# circuit.net
KiCad netlist of a schematic drawn in EasyEDA
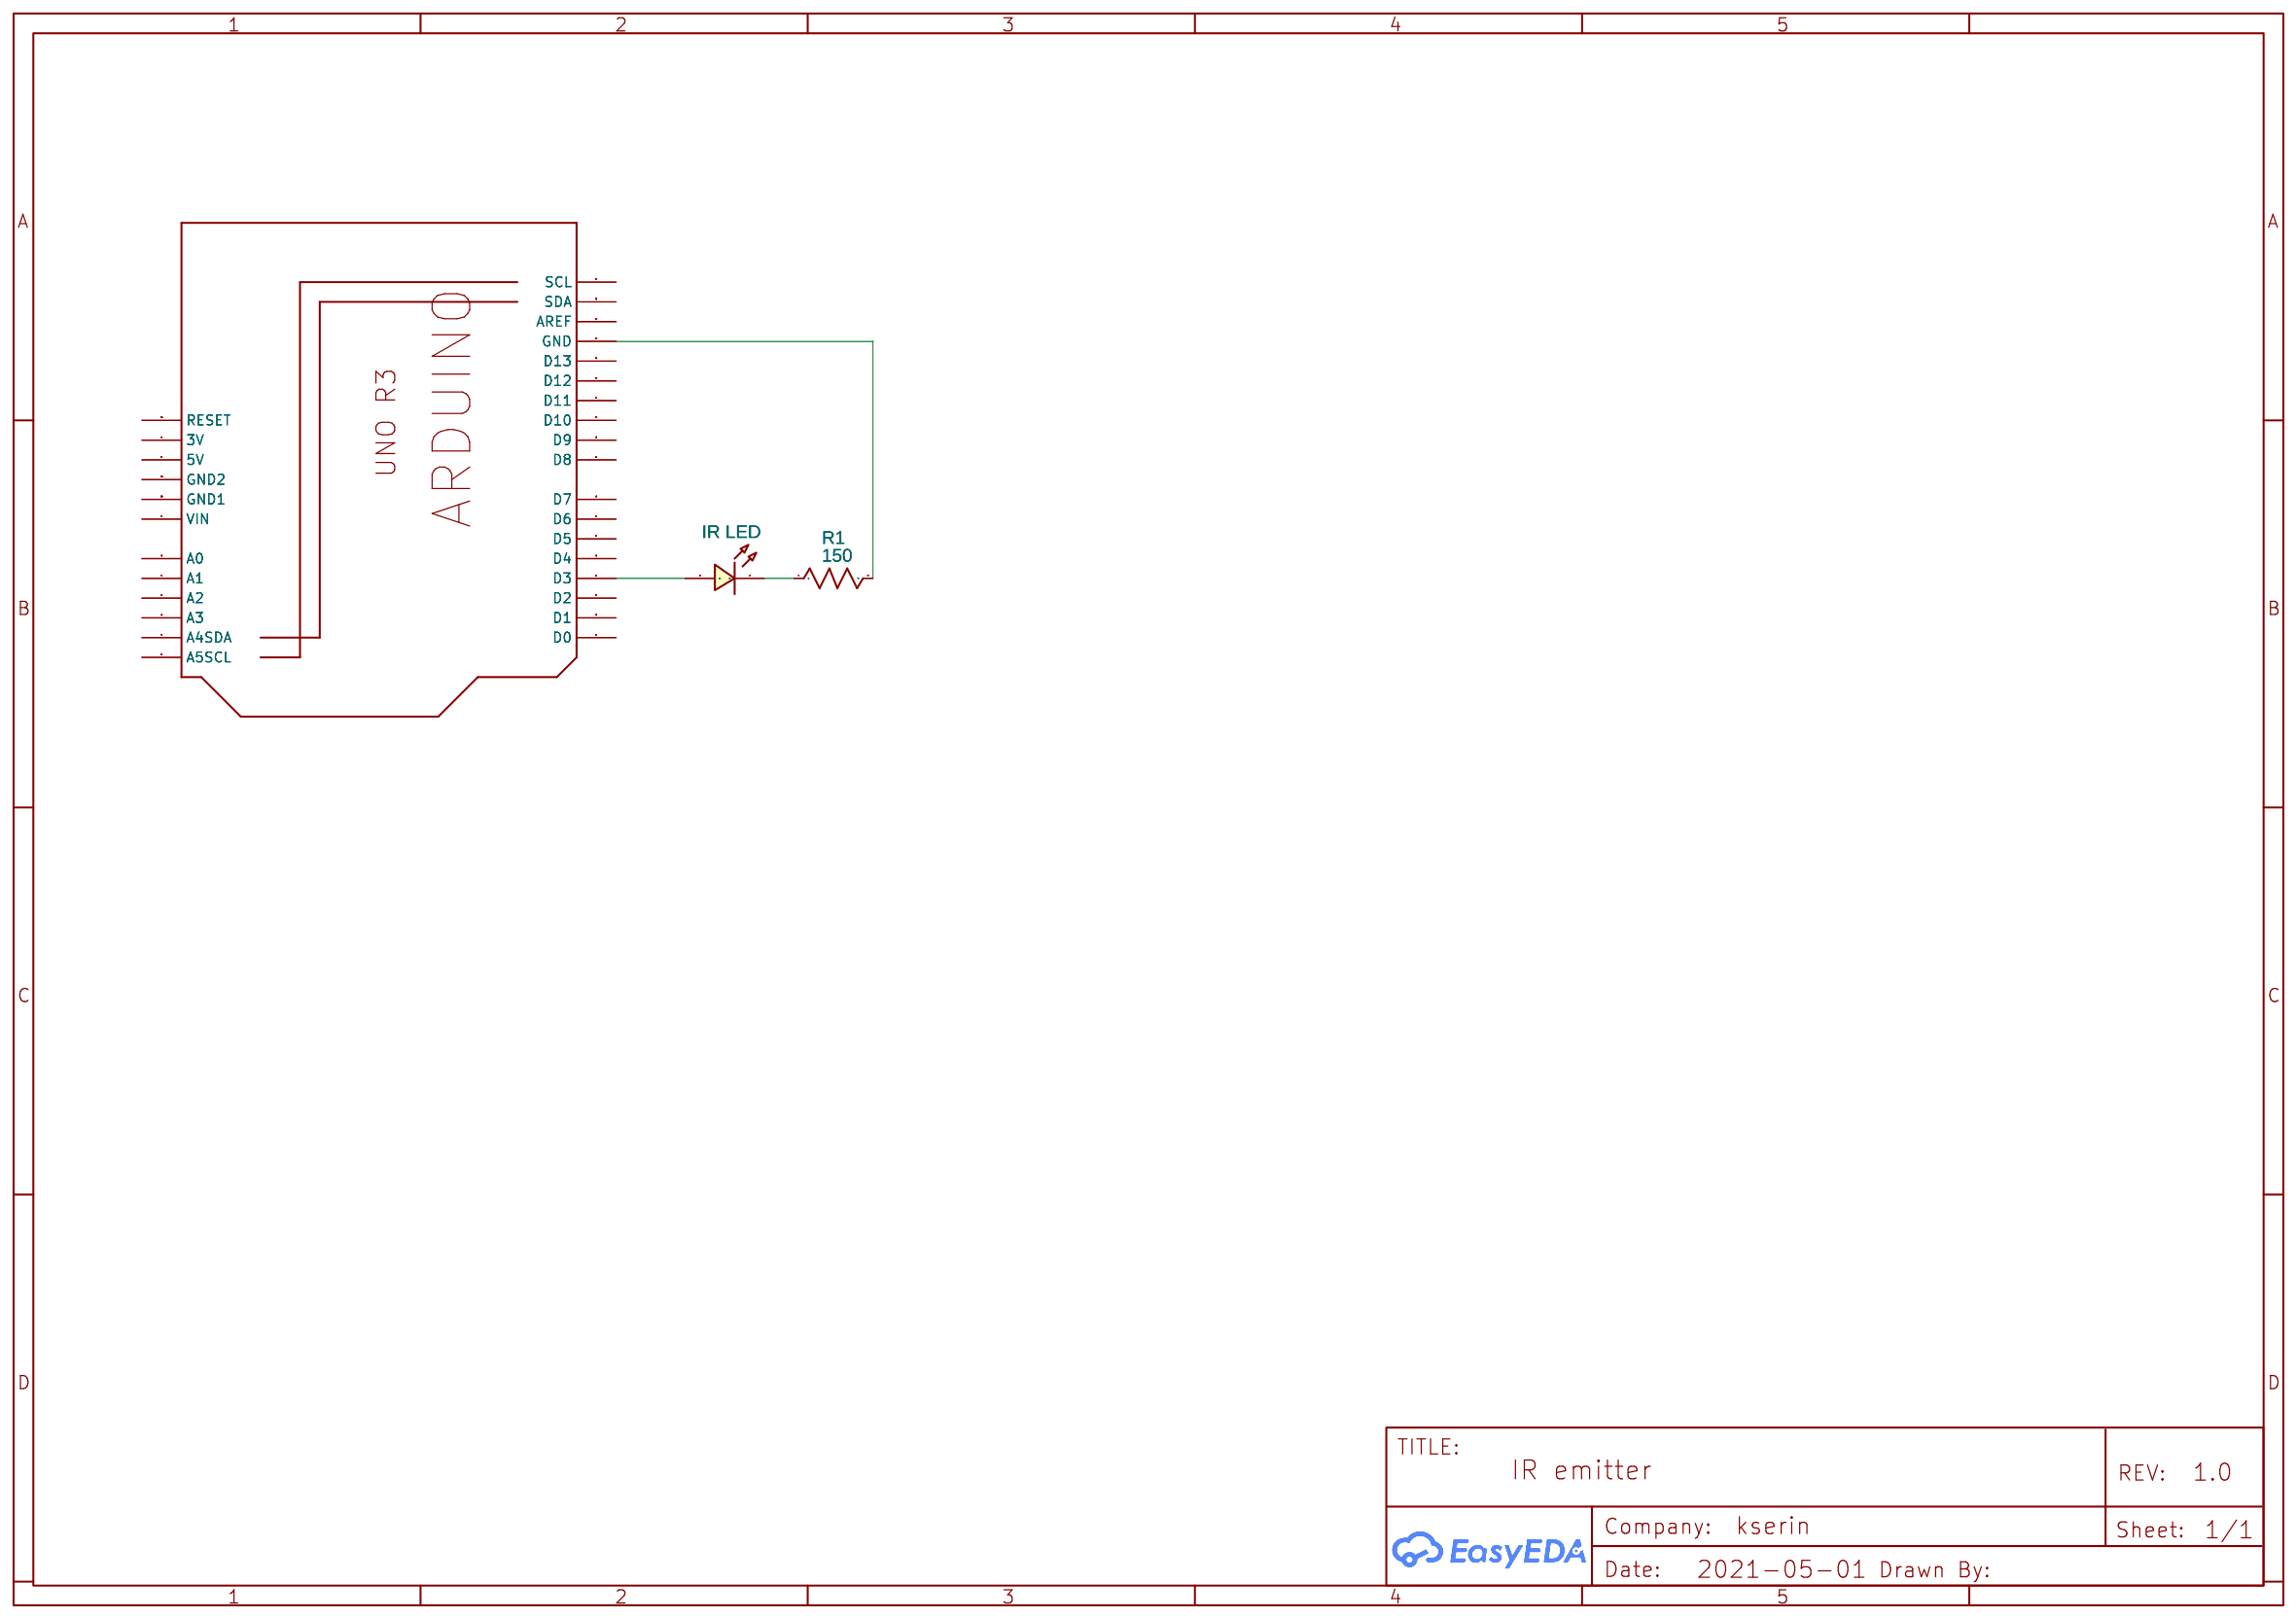
[diagram p0: schematic sheet]

(export (version "E")
  (design (tool "Eeschema 10.0.6"))
  (components
    (comp (ref "LED1")
      (value "IR LED")
      (fields
        (field (name "BOM_Manufacturer Part") "19-217/R6C-AL1M2VY/3T")
        (field (name "BOM_Supplier Part") "C72044")
      )
      (libsource (lib "") (part "LED-0603_R"))
    )
    (comp (ref "Q1")
      (value "ARDUINOR3-NOIOREF-NOTEXT")
      (libsource (lib "") (part "ARDUINOR3-NOIOREF-NOTEXT"))
    )
    (comp (ref "R1") (value "150") (libsource (lib "") (part "R_0603_US")))
  )
  (nets
    (net (code "1") (name "Net-(LED1-Pad1)") (class "Default")
      (node (ref "LED1") (pin "1") (pinfunction "1_1") (pintype "unspecified"))
      (node (ref "Q1") (pin "D3") (pinfunction "D3_D3") (pintype "unspecified"))
    )
    (net (code "2") (name "Net-(LED1-Pad2)") (class "Default")
      (node (ref "LED1") (pin "2") (pinfunction "2_2") (pintype "unspecified"))
      (node (ref "R1") (pin "1") (pinfunction "1_1") (pintype "unspecified"))
    )
    (net (code "3") (name "Net-(Q1-PadGND)") (class "Default")
      (node (ref "Q1") (pin "GND") (pinfunction "GND_GND") (pintype "passive"))
      (node (ref "R1") (pin "2") (pinfunction "2_2") (pintype "unspecified"))
    )
    (net (code "4") (name "unconnected-(Q1-A4SDA-PadA4)") (class "Default")
      (node (ref "Q1") (pin "A4") (pinfunction "A4SDA_A4") (pintype "unspecified"))
    )
    (net (code "5") (name "unconnected-(Q1-A5SCL-PadA5)") (class "Default")
      (node (ref "Q1") (pin "A5") (pinfunction "A5SCL_A5") (pintype "unspecified"))
    )
    (net (code "6") (name "unconnected-(Q1-Pad3V)") (class "Default")
      (node (ref "Q1") (pin "3V") (pinfunction "3V_3V") (pintype "passive"))
    )
    (net (code "7") (name "unconnected-(Q1-Pad5V)") (class "Default")
      (node (ref "Q1") (pin "5V") (pinfunction "5V_5V") (pintype "passive"))
    )
    (net (code "8") (name "unconnected-(Q1-PadA0)") (class "Default")
      (node (ref "Q1") (pin "A0") (pinfunction "A0_A0") (pintype "unspecified"))
    )
    (net (code "9") (name "unconnected-(Q1-PadA1)") (class "Default")
      (node (ref "Q1") (pin "A1") (pinfunction "A1_A1") (pintype "unspecified"))
    )
    (net (code "10") (name "unconnected-(Q1-PadA2)") (class "Default")
      (node (ref "Q1") (pin "A2") (pinfunction "A2_A2") (pintype "unspecified"))
    )
    (net (code "11") (name "unconnected-(Q1-PadA3)") (class "Default")
      (node (ref "Q1") (pin "A3") (pinfunction "A3_A3") (pintype "unspecified"))
    )
    (net (code "12") (name "unconnected-(Q1-PadAREF)") (class "Default")
      (node (ref "Q1") (pin "AREF") (pinfunction "AREF_AREF") (pintype "unspecified"))
    )
    (net (code "13") (name "unconnected-(Q1-PadD0)") (class "Default")
      (node (ref "Q1") (pin "D0") (pinfunction "D0_D0") (pintype "unspecified"))
    )
    (net (code "14") (name "unconnected-(Q1-PadD1)") (class "Default")
      (node (ref "Q1") (pin "D1") (pinfunction "D1_D1") (pintype "unspecified"))
    )
    (net (code "15") (name "unconnected-(Q1-PadD2)") (class "Default")
      (node (ref "Q1") (pin "D2") (pinfunction "D2_D2") (pintype "unspecified"))
    )
    (net (code "16") (name "unconnected-(Q1-PadD4)") (class "Default")
      (node (ref "Q1") (pin "D4") (pinfunction "D4_D4") (pintype "unspecified"))
    )
    (net (code "17") (name "unconnected-(Q1-PadD5)") (class "Default")
      (node (ref "Q1") (pin "D5") (pinfunction "D5_D5") (pintype "unspecified"))
    )
    (net (code "18") (name "unconnected-(Q1-PadD6)") (class "Default")
      (node (ref "Q1") (pin "D6") (pinfunction "D6_D6") (pintype "unspecified"))
    )
    (net (code "19") (name "unconnected-(Q1-PadD7)") (class "Default")
      (node (ref "Q1") (pin "D7") (pinfunction "D7_D7") (pintype "unspecified"))
    )
    (net (code "20") (name "unconnected-(Q1-PadD8)") (class "Default")
      (node (ref "Q1") (pin "D8") (pinfunction "D8_D8") (pintype "unspecified"))
    )
    (net (code "21") (name "unconnected-(Q1-PadD9)") (class "Default")
      (node (ref "Q1") (pin "D9") (pinfunction "D9_D9") (pintype "unspecified"))
    )
    (net (code "22") (name "unconnected-(Q1-PadD10)") (class "Default")
      (node (ref "Q1") (pin "D10") (pinfunction "D10_D10") (pintype "unspecified"))
    )
    (net (code "23") (name "unconnected-(Q1-PadD11)") (class "Default")
      (node (ref "Q1") (pin "D11") (pinfunction "D11_D11") (pintype "unspecified"))
    )
    (net (code "24") (name "unconnected-(Q1-PadD12)") (class "Default")
      (node (ref "Q1") (pin "D12") (pinfunction "D12_D12") (pintype "unspecified"))
    )
    (net (code "25") (name "unconnected-(Q1-PadD13)") (class "Default")
      (node (ref "Q1") (pin "D13") (pinfunction "D13_D13") (pintype "unspecified"))
    )
    (net (code "26") (name "unconnected-(Q1-PadGND1)") (class "Default")
      (node (ref "Q1") (pin "GND1") (pinfunction "GND1_GND1") (pintype "passive"))
    )
    (net (code "27") (name "unconnected-(Q1-PadGND2)") (class "Default")
      (node (ref "Q1") (pin "GND2") (pinfunction "GND2_GND2") (pintype "passive"))
    )
    (net (code "28") (name "unconnected-(Q1-PadRESET)") (class "Default")
      (node (ref "Q1") (pin "RESET") (pinfunction "RESET_RESET") (pintype "unspecified"))
    )
    (net (code "29") (name "unconnected-(Q1-PadSCL)") (class "Default")
      (node (ref "Q1") (pin "SCL") (pinfunction "SCL_SCL") (pintype "unspecified"))
    )
    (net (code "30") (name "unconnected-(Q1-PadSDA)") (class "Default")
      (node (ref "Q1") (pin "SDA") (pinfunction "SDA_SDA") (pintype "unspecified"))
    )
    (net (code "31") (name "unconnected-(Q1-PadVIN)") (class "Default")
      (node (ref "Q1") (pin "VIN") (pinfunction "VIN_VIN") (pintype "passive"))
    )
  )
)
